# amiga_external_floppy_adapter_rev1.net
KiCad netlist of a schematic drawn in EAGLE
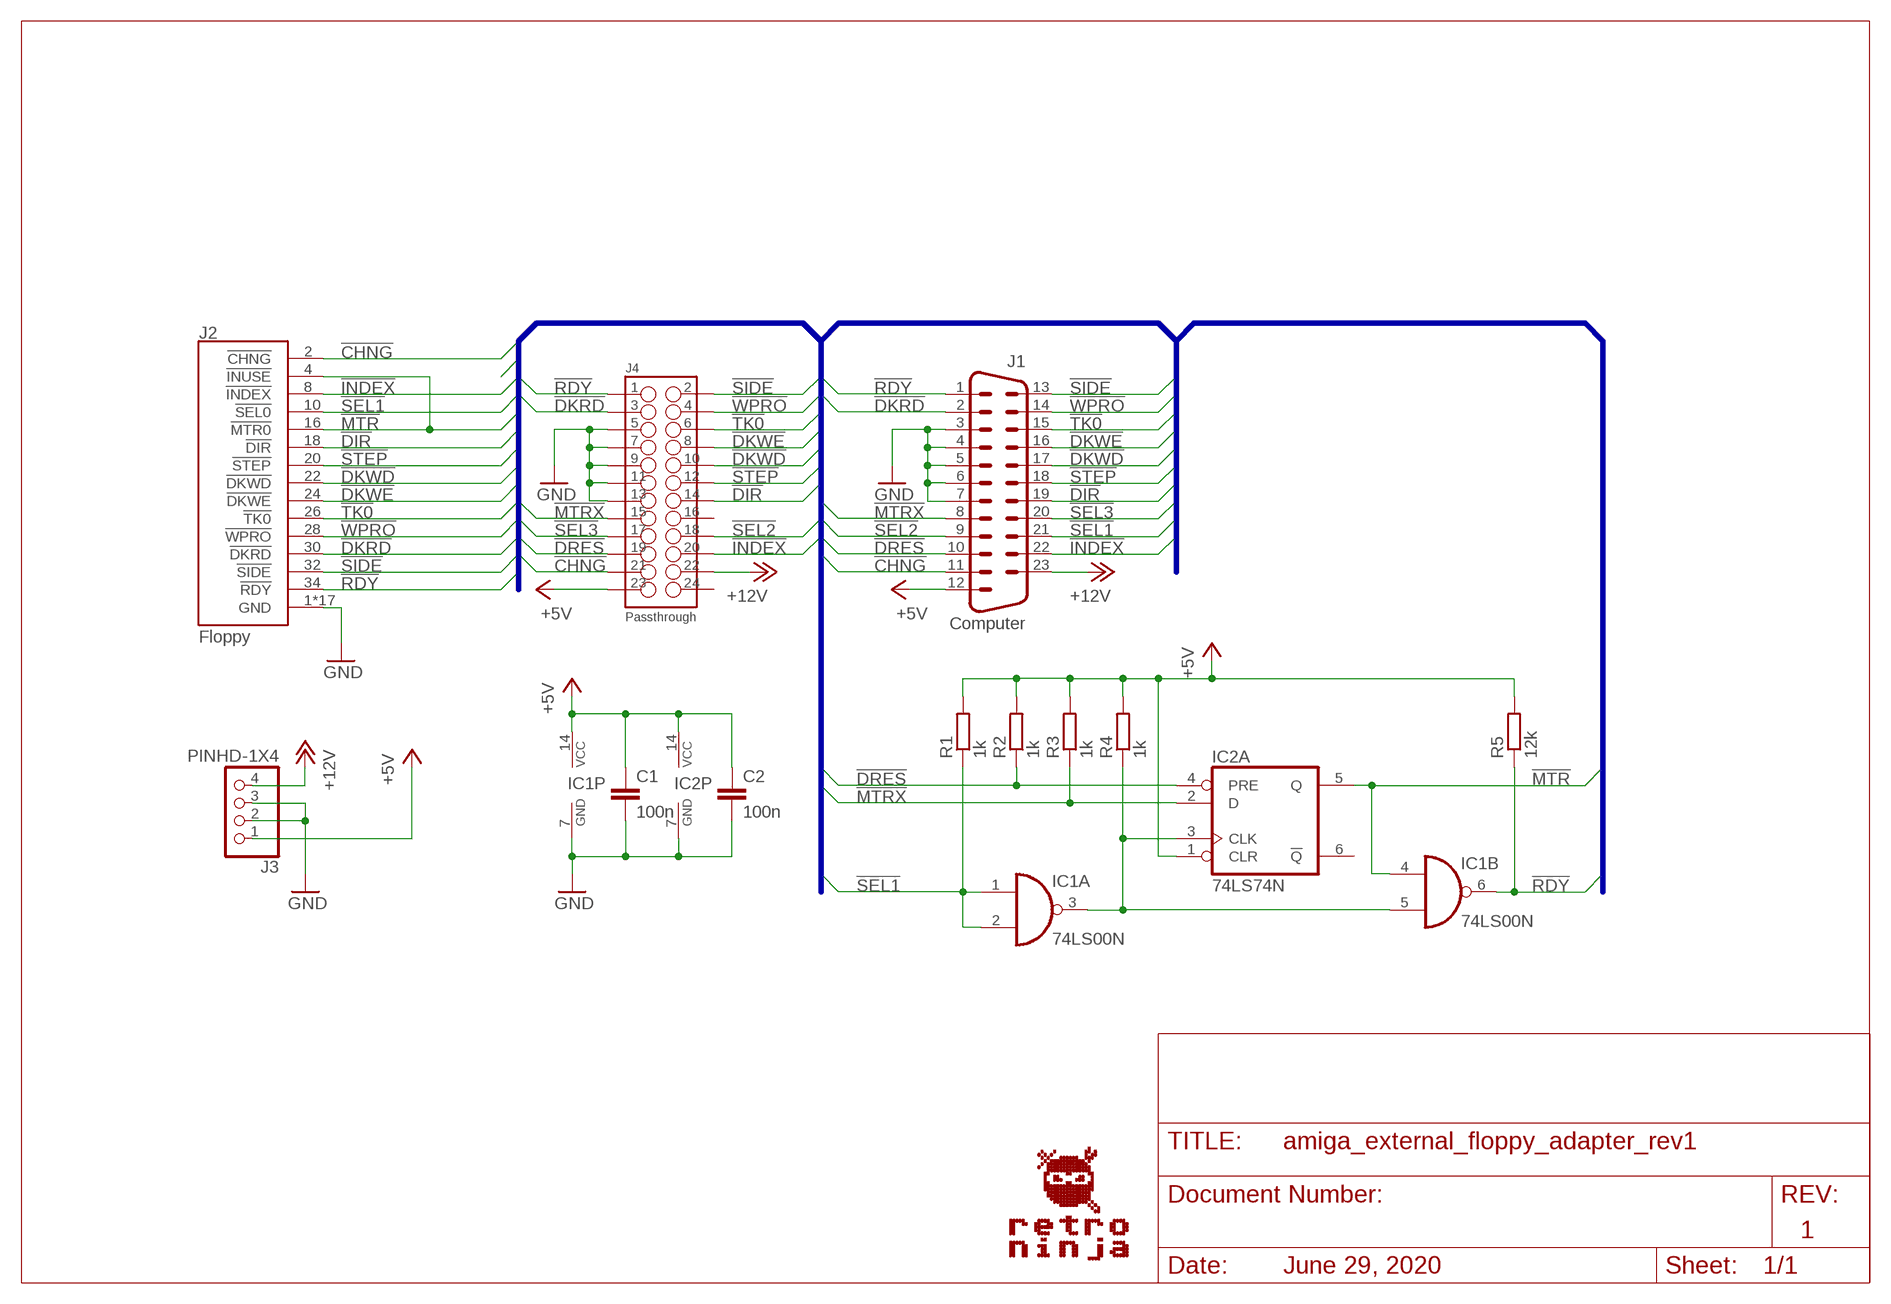
[diagram p0: schematic, sheet 1]

(export (version "E")
  (design (tool "Eeschema 10.0.6"))
  (components
    (comp (ref "C1")
      (value "100n")
      (footprint "eagle-import:C025-025X050")
      (libsource (lib "eagle-import") (part "C-EU025-025X050"))
    )
    (comp (ref "C2")
      (value "100n")
      (footprint "eagle-import:C025-025X050")
      (libsource (lib "eagle-import") (part "C-EU025-025X050"))
    )
    (comp (ref "IC1")
      (value "74LS00N")
      (footprint "eagle-import:DIL14")
      (libsource (lib "eagle-import") (part "7400NLS"))
    )
    (comp (ref "IC2")
      (value "74LS74N")
      (footprint "eagle-import:DIL14")
      (libsource (lib "eagle-import") (part "7474NLS"))
    )
    (comp (ref "J1")
      (value "Computer")
      (footprint "eagle-import:DSUB_M23D")
      (libsource (lib "eagle-import") (part "DSUB_M23"))
    )
    (comp (ref "J2")
      (value "Floppy")
      (footprint "eagle-import:HEADER_2X17_WALLED")
      (libsource (lib "eagle-import") (part "AMIGA_FLOPPYDRV_CONNECTOR/IDC"))
    )
    (comp (ref "J3")
      (value "PINHD-1X4")
      (footprint "eagle-import:1X04")
      (libsource (lib "eagle-import") (part "PINHD-1X4"))
    )
    (comp (ref "J4")
      (value "Passthrough")
      (footprint "eagle-import:HEADER_2X12_WALLED")
      (libsource (lib "eagle-import") (part "HEADER_2X12/IDC"))
    )
    (comp (ref "R1")
      (value "1k")
      (footprint "eagle-import:0207_10")
      (libsource (lib "eagle-import") (part "R-EU_0207/10"))
    )
    (comp (ref "R2")
      (value "1k")
      (footprint "eagle-import:0207_10")
      (libsource (lib "eagle-import") (part "R-EU_0207/10"))
    )
    (comp (ref "R3")
      (value "1k")
      (footprint "eagle-import:0207_10")
      (libsource (lib "eagle-import") (part "R-EU_0207/10"))
    )
    (comp (ref "R4")
      (value "1k")
      (footprint "eagle-import:0207_10")
      (libsource (lib "eagle-import") (part "R-EU_0207/10"))
    )
    (comp (ref "R5")
      (value "12k")
      (footprint "eagle-import:0207_10")
      (libsource (lib "eagle-import") (part "R-EU_0207/10"))
    )
  )
  (nets
    (net (code "1") (name "+5V") (class "Default")
      (node (ref "C1") (pin "1") (pinfunction "1_1") (pintype "passive"))
      (node (ref "C2") (pin "1") (pinfunction "1_1") (pintype "passive"))
      (node (ref "IC1") (pin "14") (pinfunction "VCC_14") (pintype "power_in"))
      (node (ref "IC2") (pin "1") (pinfunction "CLR_1") (pintype "input"))
      (node (ref "IC2") (pin "14") (pinfunction "VCC_14") (pintype "power_in"))
      (node (ref "J1") (pin "12") (pinfunction "12_12") (pintype "passive"))
      (node (ref "J3") (pin "1") (pinfunction "1_1") (pintype "passive"))
      (node (ref "J4") (pin "23") (pinfunction "23_23") (pintype "bidirectional"))
      (node (ref "R1") (pin "2") (pinfunction "2_2") (pintype "passive"))
      (node (ref "R2") (pin "2") (pinfunction "2_2") (pintype "passive"))
      (node (ref "R3") (pin "2") (pinfunction "2_2") (pintype "passive"))
      (node (ref "R4") (pin "2") (pinfunction "2_2") (pintype "passive"))
      (node (ref "R5") (pin "2") (pinfunction "2_2") (pintype "passive"))
    )
    (net (code "2") (name "+12V") (class "Default")
      (node (ref "J1") (pin "23") (pinfunction "23_23") (pintype "passive"))
      (node (ref "J3") (pin "4") (pinfunction "4_4") (pintype "passive"))
      (node (ref "J4") (pin "22") (pinfunction "22_22") (pintype "bidirectional"))
    )
    (net (code "3") (name "/~{CHNG}") (class "Default")
      (node (ref "J1") (pin "11") (pinfunction "11_11") (pintype "passive"))
      (node (ref "J2") (pin "2") (pinfunction "~{CHNG}_2") (pintype "bidirectional"))
      (node (ref "J4") (pin "21") (pinfunction "21_21") (pintype "bidirectional"))
    )
    (net (code "4") (name "/~{DIR}") (class "Default")
      (node (ref "J1") (pin "19") (pinfunction "19_19") (pintype "passive"))
      (node (ref "J2") (pin "18") (pinfunction "~{DIR}_18") (pintype "bidirectional"))
      (node (ref "J4") (pin "14") (pinfunction "14_14") (pintype "bidirectional"))
    )
    (net (code "5") (name "/~{DKRD}") (class "Default")
      (node (ref "J1") (pin "2") (pinfunction "2_2") (pintype "passive"))
      (node (ref "J2") (pin "30") (pinfunction "~{DKRD}_30") (pintype "bidirectional"))
      (node (ref "J4") (pin "3") (pinfunction "3_3") (pintype "bidirectional"))
    )
    (net (code "6") (name "/~{DKWD}") (class "Default")
      (node (ref "J1") (pin "17") (pinfunction "17_17") (pintype "passive"))
      (node (ref "J2") (pin "22") (pinfunction "~{DKWD}_22") (pintype "bidirectional"))
      (node (ref "J4") (pin "10") (pinfunction "10_10") (pintype "bidirectional"))
    )
    (net (code "7") (name "/~{DKWE}") (class "Default")
      (node (ref "J1") (pin "16") (pinfunction "16_16") (pintype "passive"))
      (node (ref "J2") (pin "24") (pinfunction "~{DKWE}_24") (pintype "bidirectional"))
      (node (ref "J4") (pin "8") (pinfunction "8_8") (pintype "bidirectional"))
    )
    (net (code "8") (name "/~{DRES}") (class "Default")
      (node (ref "IC2") (pin "4") (pinfunction "PRE_4") (pintype "input"))
      (node (ref "J1") (pin "10") (pinfunction "10_10") (pintype "passive"))
      (node (ref "J4") (pin "19") (pinfunction "19_19") (pintype "bidirectional"))
      (node (ref "R2") (pin "1") (pinfunction "1_1") (pintype "passive"))
    )
    (net (code "9") (name "/~{INDEX}") (class "Default")
      (node (ref "J1") (pin "22") (pinfunction "22_22") (pintype "passive"))
      (node (ref "J2") (pin "8") (pinfunction "~{INDEX}_8") (pintype "bidirectional"))
      (node (ref "J4") (pin "20") (pinfunction "20_20") (pintype "bidirectional"))
    )
    (net (code "10") (name "/~{MTRX}") (class "Default")
      (node (ref "IC2") (pin "2") (pinfunction "D_2") (pintype "input"))
      (node (ref "J1") (pin "8") (pinfunction "8_8") (pintype "passive"))
      (node (ref "J4") (pin "15") (pinfunction "15_15") (pintype "bidirectional"))
      (node (ref "R3") (pin "1") (pinfunction "1_1") (pintype "passive"))
    )
    (net (code "11") (name "/~{MTR}") (class "Default")
      (node (ref "IC1") (pin "4") (pinfunction "I0_4") (pintype "input"))
      (node (ref "IC2") (pin "5") (pinfunction "Q_5") (pintype "output"))
      (node (ref "J2") (pin "16") (pinfunction "~{MTR0}_16") (pintype "bidirectional"))
      (node (ref "J2") (pin "4") (pinfunction "~{INUSE}_4") (pintype "bidirectional"))
    )
    (net (code "12") (name "/~{RDY}") (class "Default")
      (node (ref "IC1") (pin "6") (pinfunction "O_6") (pintype "output"))
      (node (ref "J1") (pin "1") (pinfunction "1_1") (pintype "passive"))
      (node (ref "J2") (pin "34") (pinfunction "~{RDY}_34") (pintype "bidirectional"))
      (node (ref "J4") (pin "1") (pinfunction "1_1") (pintype "bidirectional"))
      (node (ref "R5") (pin "1") (pinfunction "1_1") (pintype "passive"))
    )
    (net (code "13") (name "/~{SEL1}") (class "Default")
      (node (ref "IC1") (pin "1") (pinfunction "I0_1") (pintype "input"))
      (node (ref "IC1") (pin "2") (pinfunction "I1_2") (pintype "input"))
      (node (ref "J1") (pin "21") (pinfunction "21_21") (pintype "passive"))
      (node (ref "J2") (pin "10") (pinfunction "~{SEL0}_10") (pintype "bidirectional"))
      (node (ref "R1") (pin "1") (pinfunction "1_1") (pintype "passive"))
    )
    (net (code "14") (name "/~{SEL2}") (class "Default")
      (node (ref "J1") (pin "9") (pinfunction "9_9") (pintype "passive"))
      (node (ref "J4") (pin "18") (pinfunction "18_18") (pintype "bidirectional"))
    )
    (net (code "15") (name "/~{SEL3}") (class "Default")
      (node (ref "J1") (pin "20") (pinfunction "20_20") (pintype "passive"))
      (node (ref "J4") (pin "17") (pinfunction "17_17") (pintype "bidirectional"))
    )
    (net (code "16") (name "/~{SIDE}") (class "Default")
      (node (ref "J1") (pin "13") (pinfunction "13_13") (pintype "passive"))
      (node (ref "J2") (pin "32") (pinfunction "~{SIDE}_32") (pintype "bidirectional"))
      (node (ref "J4") (pin "2") (pinfunction "2_2") (pintype "bidirectional"))
    )
    (net (code "17") (name "/~{STEP}") (class "Default")
      (node (ref "J1") (pin "18") (pinfunction "18_18") (pintype "passive"))
      (node (ref "J2") (pin "20") (pinfunction "~{STEP}_20") (pintype "bidirectional"))
      (node (ref "J4") (pin "12") (pinfunction "12_12") (pintype "bidirectional"))
    )
    (net (code "18") (name "/~{TK0}") (class "Default")
      (node (ref "J1") (pin "15") (pinfunction "15_15") (pintype "passive"))
      (node (ref "J2") (pin "26") (pinfunction "~{TK0}_26") (pintype "bidirectional"))
      (node (ref "J4") (pin "6") (pinfunction "6_6") (pintype "bidirectional"))
    )
    (net (code "19") (name "/~{WPRO}") (class "Default")
      (node (ref "J1") (pin "14") (pinfunction "14_14") (pintype "passive"))
      (node (ref "J2") (pin "28") (pinfunction "~{WPRO}_28") (pintype "bidirectional"))
      (node (ref "J4") (pin "4") (pinfunction "4_4") (pintype "bidirectional"))
    )
    (net (code "20") (name "GND") (class "Default")
      (node (ref "C1") (pin "2") (pinfunction "2_2") (pintype "passive"))
      (node (ref "C2") (pin "2") (pinfunction "2_2") (pintype "passive"))
      (node (ref "IC1") (pin "7") (pinfunction "GND_7") (pintype "power_in"))
      (node (ref "IC2") (pin "7") (pinfunction "GND_7") (pintype "power_in"))
      (node (ref "J1") (pin "3") (pinfunction "3_3") (pintype "passive"))
      (node (ref "J1") (pin "4") (pinfunction "4_4") (pintype "passive"))
      (node (ref "J1") (pin "5") (pinfunction "5_5") (pintype "passive"))
      (node (ref "J1") (pin "6") (pinfunction "6_6") (pintype "passive"))
      (node (ref "J1") (pin "7") (pinfunction "7_7") (pintype "passive"))
      (node (ref "J2") (pin "1") (pinfunction "GND_1") (pintype "power_in"))
      (node (ref "J2") (pin "11") (pinfunction "GND_11") (pintype "power_in"))
      (node (ref "J2") (pin "13") (pinfunction "GND_13") (pintype "power_in"))
      (node (ref "J2") (pin "15") (pinfunction "GND_15") (pintype "power_in"))
      (node (ref "J2") (pin "17") (pinfunction "GND_17") (pintype "power_in"))
      (node (ref "J2") (pin "19") (pinfunction "GND_19") (pintype "power_in"))
      (node (ref "J2") (pin "21") (pinfunction "GND_21") (pintype "power_in"))
      (node (ref "J2") (pin "23") (pinfunction "GND_23") (pintype "power_in"))
      (node (ref "J2") (pin "25") (pinfunction "GND_25") (pintype "power_in"))
      (node (ref "J2") (pin "27") (pinfunction "GND_27") (pintype "power_in"))
      (node (ref "J2") (pin "29") (pinfunction "GND_29") (pintype "power_in"))
      (node (ref "J2") (pin "3") (pinfunction "GND_3") (pintype "power_in"))
      (node (ref "J2") (pin "31") (pinfunction "GND_31") (pintype "power_in"))
      (node (ref "J2") (pin "33") (pinfunction "GND_33") (pintype "power_in"))
      (node (ref "J2") (pin "5") (pinfunction "GND_5") (pintype "power_in"))
      (node (ref "J2") (pin "7") (pinfunction "GND_7") (pintype "power_in"))
      (node (ref "J2") (pin "9") (pinfunction "GND_9") (pintype "power_in"))
      (node (ref "J3") (pin "2") (pinfunction "2_2") (pintype "passive"))
      (node (ref "J3") (pin "3") (pinfunction "3_3") (pintype "passive"))
      (node (ref "J4") (pin "11") (pinfunction "11_11") (pintype "bidirectional"))
      (node (ref "J4") (pin "13") (pinfunction "13_13") (pintype "bidirectional"))
      (node (ref "J4") (pin "5") (pinfunction "5_5") (pintype "bidirectional"))
      (node (ref "J4") (pin "7") (pinfunction "7_7") (pintype "bidirectional"))
      (node (ref "J4") (pin "9") (pinfunction "9_9") (pintype "bidirectional"))
    )
    (net (code "21") (name "Net-(IC1A-O)") (class "Default")
      (node (ref "IC1") (pin "3") (pinfunction "O_3") (pintype "output"))
      (node (ref "IC1") (pin "5") (pinfunction "I1_5") (pintype "input"))
      (node (ref "IC2") (pin "3") (pinfunction "CLK_3") (pintype "input"))
      (node (ref "R4") (pin "1") (pinfunction "1_1") (pintype "passive"))
    )
    (net (code "22") (name "unconnected-(IC2A-~{Q}-Pad6)") (class "Default")
      (node (ref "IC2") (pin "6") (pinfunction "~{Q}_6") (pintype "output"))
    )
    (net (code "23") (name "unconnected-(J4-Pad16)") (class "Default")
      (node (ref "J4") (pin "16") (pinfunction "16_16") (pintype "bidirectional"))
    )
    (net (code "24") (name "unconnected-(J4-Pad24)") (class "Default")
      (node (ref "J4") (pin "24") (pinfunction "24_24") (pintype "bidirectional"))
    )
  )
)
